# R2P_Sonar_module.net
KiCad netlist of a schematic drawn in EAGLE
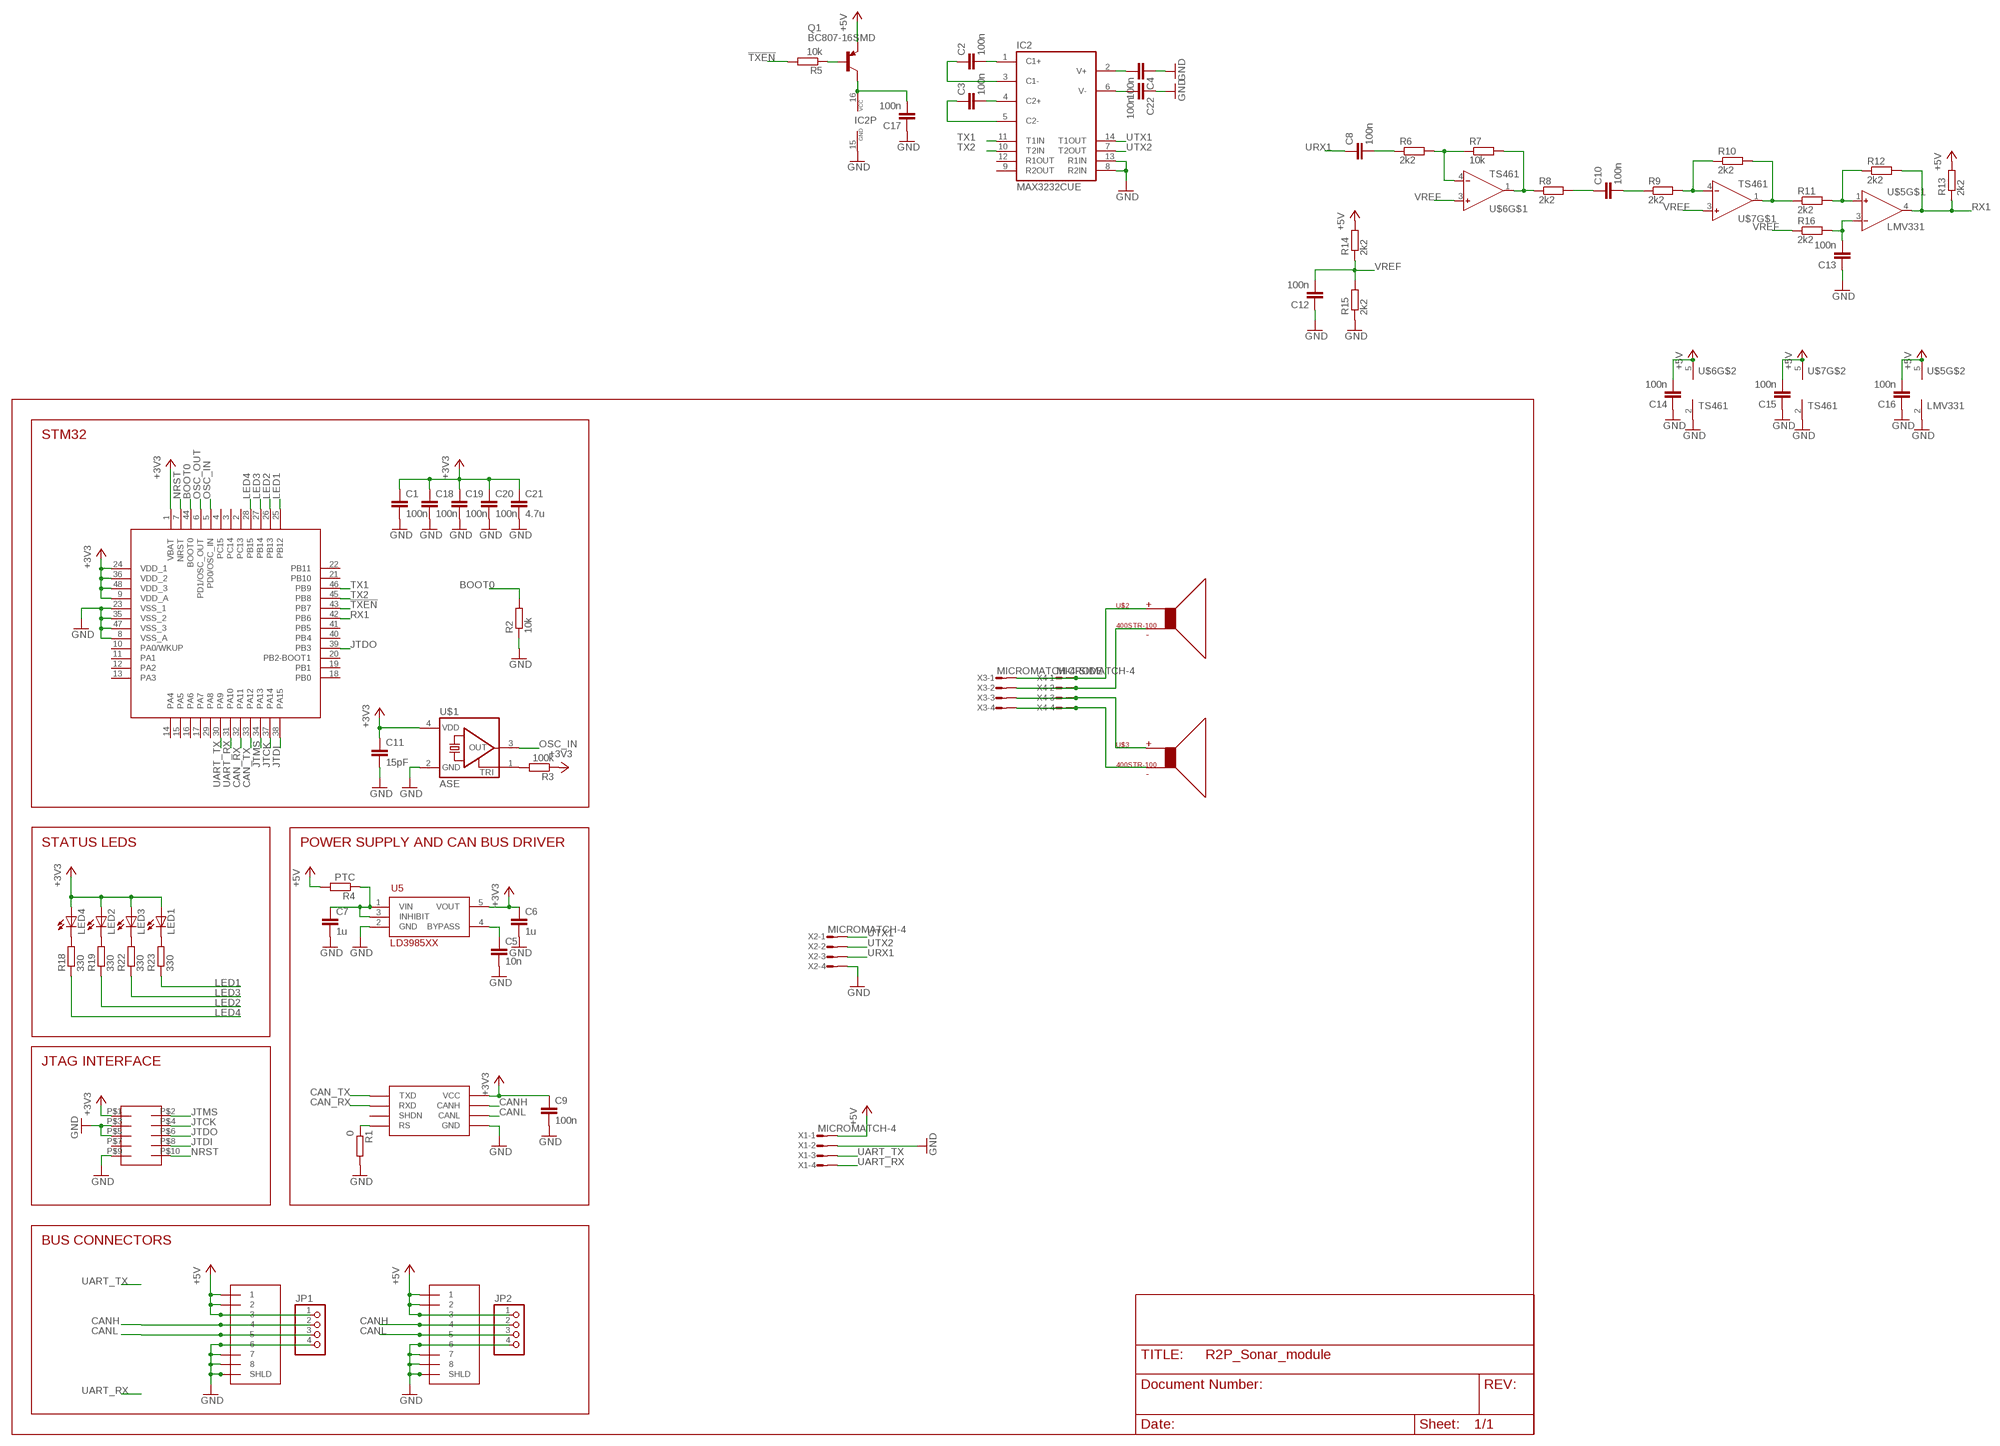
[diagram p0: schematic, sheet 1]

(export (version "E")
  (design (tool "Eeschema 10.0.6"))
  (components
    (comp (ref "1")
      (value "RJ45-43860")
      (footprint "eagle-import:0438600010")
      (libsource (lib "eagle-import") (part "RJ45-43860"))
    )
    (comp (ref "2")
      (value "RJ45-43860")
      (footprint "eagle-import:0438600010")
      (libsource (lib "eagle-import") (part "RJ45-43860"))
    )
    (comp (ref "C1")
      (value "100n")
      (footprint "eagle-import:C0603")
      (libsource (lib "eagle-import") (part "C-EUC0603"))
    )
    (comp (ref "C2")
      (value "100n")
      (footprint "eagle-import:C0603")
      (libsource (lib "eagle-import") (part "C-EUC0603"))
    )
    (comp (ref "C3")
      (value "100n")
      (footprint "eagle-import:C0603")
      (libsource (lib "eagle-import") (part "C-EUC0603"))
    )
    (comp (ref "C4")
      (value "100n")
      (footprint "eagle-import:C0603")
      (libsource (lib "eagle-import") (part "C-EUC0603"))
    )
    (comp (ref "C5")
      (value "10n")
      (footprint "eagle-import:C0603")
      (libsource (lib "eagle-import") (part "C-EUC0603"))
    )
    (comp (ref "C6")
      (value "1u")
      (footprint "eagle-import:C0603")
      (libsource (lib "eagle-import") (part "C-EUC0603"))
    )
    (comp (ref "C7")
      (value "1u")
      (footprint "eagle-import:C0603")
      (libsource (lib "eagle-import") (part "C-EUC0603"))
    )
    (comp (ref "C8")
      (value "100n")
      (footprint "eagle-import:C0603")
      (libsource (lib "eagle-import") (part "C-EUC0603"))
    )
    (comp (ref "C9")
      (value "100n")
      (footprint "eagle-import:C0603")
      (libsource (lib "eagle-import") (part "C-EUC0603"))
    )
    (comp (ref "C10")
      (value "100n")
      (footprint "eagle-import:C0603")
      (libsource (lib "eagle-import") (part "C-EUC0603"))
    )
    (comp (ref "C11")
      (value "15pF")
      (footprint "eagle-import:C0603")
      (libsource (lib "eagle-import") (part "C-EUC0603"))
    )
    (comp (ref "C12")
      (value "100n")
      (footprint "eagle-import:C0603")
      (libsource (lib "eagle-import") (part "C-EUC0603"))
    )
    (comp (ref "C13")
      (value "100n")
      (footprint "eagle-import:C0603")
      (libsource (lib "eagle-import") (part "C-EUC0603"))
    )
    (comp (ref "C14")
      (value "100n")
      (footprint "eagle-import:C0603")
      (libsource (lib "eagle-import") (part "C-EUC0603"))
    )
    (comp (ref "C15")
      (value "100n")
      (footprint "eagle-import:C0603")
      (libsource (lib "eagle-import") (part "C-EUC0603"))
    )
    (comp (ref "C16")
      (value "100n")
      (footprint "eagle-import:C0603")
      (libsource (lib "eagle-import") (part "C-EUC0603"))
    )
    (comp (ref "C17")
      (value "100n")
      (footprint "eagle-import:C0603")
      (libsource (lib "eagle-import") (part "C-EUC0603"))
    )
    (comp (ref "C18")
      (value "100n")
      (footprint "eagle-import:C0603")
      (libsource (lib "eagle-import") (part "C-EUC0603"))
    )
    (comp (ref "C19")
      (value "100n")
      (footprint "eagle-import:C0603")
      (libsource (lib "eagle-import") (part "C-EUC0603"))
    )
    (comp (ref "C20")
      (value "100n")
      (footprint "eagle-import:C0603")
      (libsource (lib "eagle-import") (part "C-EUC0603"))
    )
    (comp (ref "C21")
      (value "4.7u")
      (footprint "eagle-import:C0805")
      (libsource (lib "eagle-import") (part "C-EUC0805"))
    )
    (comp (ref "C22")
      (value "100n")
      (footprint "eagle-import:C0603")
      (libsource (lib "eagle-import") (part "C-EUC0603"))
    )
    (comp (ref "IC2")
      (value "MAX3232CUE")
      (footprint "eagle-import:TSSOP16")
      (fields (field (name "MF") "MAXIM") (field (name "MPN") "MAX3232CUE+"))
      (libsource (lib "eagle-import") (part "MAX3232UEC"))
    )
    (comp (ref "JP1")
      (value "PINHD-1X4")
      (footprint "eagle-import:1X04")
      (libsource (lib "eagle-import") (part "PINHD-1X4"))
    )
    (comp (ref "JP2")
      (value "PINHD-1X4")
      (footprint "eagle-import:1X04")
      (libsource (lib "eagle-import") (part "PINHD-1X4"))
    )
    (comp (ref "LED1")
      (value "LEDCHIPLED_0805")
      (footprint "eagle-import:CHIPLED_0805")
      (libsource (lib "eagle-import") (part "LEDCHIPLED_0805"))
    )
    (comp (ref "LED2")
      (value "LEDCHIPLED_0805")
      (footprint "eagle-import:CHIPLED_0805")
      (libsource (lib "eagle-import") (part "LEDCHIPLED_0805"))
    )
    (comp (ref "LED3")
      (value "LEDCHIPLED_0805")
      (footprint "eagle-import:CHIPLED_0805")
      (libsource (lib "eagle-import") (part "LEDCHIPLED_0805"))
    )
    (comp (ref "LED4")
      (value "LEDCHIPLED_0805")
      (footprint "eagle-import:CHIPLED_0805")
      (libsource (lib "eagle-import") (part "LEDCHIPLED_0805"))
    )
    (comp (ref "Q1")
      (value "BC807-16SMD")
      (footprint "eagle-import:SOT23-BEC")
      (libsource (lib "eagle-import") (part "BC807SMD-16"))
    )
    (comp (ref "R1")
      (value "0")
      (footprint "eagle-import:R0603")
      (libsource (lib "eagle-import") (part "R-EU_R0603"))
    )
    (comp (ref "R2")
      (value "10k")
      (footprint "eagle-import:R0603")
      (libsource (lib "eagle-import") (part "R-EU_R0603"))
    )
    (comp (ref "R3")
      (value "100k")
      (footprint "eagle-import:R0603")
      (libsource (lib "eagle-import") (part "R-EU_R0603"))
    )
    (comp (ref "R4")
      (value "PTC")
      (footprint "eagle-import:R0603")
      (libsource (lib "eagle-import") (part "R-EU_R0603"))
    )
    (comp (ref "R5")
      (value "10k")
      (footprint "eagle-import:R0603")
      (libsource (lib "eagle-import") (part "R-EU_R0603"))
    )
    (comp (ref "R6")
      (value "2k2")
      (footprint "eagle-import:R0603")
      (libsource (lib "eagle-import") (part "R-EU_R0603"))
    )
    (comp (ref "R7")
      (value "10k")
      (footprint "eagle-import:R0603")
      (libsource (lib "eagle-import") (part "R-EU_R0603"))
    )
    (comp (ref "R8")
      (value "2k2")
      (footprint "eagle-import:R0603")
      (libsource (lib "eagle-import") (part "R-EU_R0603"))
    )
    (comp (ref "R9")
      (value "2k2")
      (footprint "eagle-import:R0603")
      (libsource (lib "eagle-import") (part "R-EU_R0603"))
    )
    (comp (ref "R10")
      (value "2k2")
      (footprint "eagle-import:R0603")
      (libsource (lib "eagle-import") (part "R-EU_R0603"))
    )
    (comp (ref "R11")
      (value "2k2")
      (footprint "eagle-import:R0603")
      (libsource (lib "eagle-import") (part "R-EU_R0603"))
    )
    (comp (ref "R12")
      (value "2k2")
      (footprint "eagle-import:R0603")
      (libsource (lib "eagle-import") (part "R-EU_R0603"))
    )
    (comp (ref "R13")
      (value "2k2")
      (footprint "eagle-import:R0603")
      (libsource (lib "eagle-import") (part "R-EU_R0603"))
    )
    (comp (ref "R14")
      (value "2k2")
      (footprint "eagle-import:R0603")
      (libsource (lib "eagle-import") (part "R-EU_R0603"))
    )
    (comp (ref "R15")
      (value "2k2")
      (footprint "eagle-import:R0603")
      (libsource (lib "eagle-import") (part "R-EU_R0603"))
    )
    (comp (ref "R16")
      (value "2k2")
      (footprint "eagle-import:R0603")
      (libsource (lib "eagle-import") (part "R-EU_R0603"))
    )
    (comp (ref "R18")
      (value "330")
      (footprint "eagle-import:R0603")
      (libsource (lib "eagle-import") (part "R-EU_R0603"))
    )
    (comp (ref "R19")
      (value "330")
      (footprint "eagle-import:R0603")
      (libsource (lib "eagle-import") (part "R-EU_R0603"))
    )
    (comp (ref "R22")
      (value "330")
      (footprint "eagle-import:R0603")
      (libsource (lib "eagle-import") (part "R-EU_R0603"))
    )
    (comp (ref "R23")
      (value "330")
      (footprint "eagle-import:R0603")
      (libsource (lib "eagle-import") (part "R-EU_R0603"))
    )
    (comp (ref "SOT1")
      (value "MAX3051")
      (footprint "eagle-import:SOT23-8L")
      (libsource (lib "eagle-import") (part "MAX3051"))
    )
    (comp (ref "U$1")
      (value "ASE")
      (footprint "eagle-import:ASE")
      (libsource (lib "eagle-import") (part "ASE"))
    )
    (comp (ref "U$2")
      (value "400STR-100")
      (footprint "eagle-import:400STR100")
      (libsource (lib "eagle-import") (part "400STR-100"))
    )
    (comp (ref "U$3")
      (value "400STR-100")
      (footprint "eagle-import:400STR100")
      (libsource (lib "eagle-import") (part "400STR-100"))
    )
    (comp (ref "U$4")
      (value "FTSH-105")
      (footprint "eagle-import:FTSH-105")
      (libsource (lib "eagle-import") (part "FTSH-105"))
    )
    (comp (ref "U$5")
      (value "LMV331")
      (footprint "eagle-import:SOT23-5L")
      (libsource (lib "eagle-import") (part "LMV331"))
    )
    (comp (ref "U$6")
      (value "TS461")
      (footprint "eagle-import:SOT23-5L")
      (libsource (lib "eagle-import") (part "TS461"))
    )
    (comp (ref "U$7")
      (value "TS461")
      (footprint "eagle-import:SOT23-5L")
      (libsource (lib "eagle-import") (part "TS461"))
    )
    (comp (ref "U1")
      (value "STM32F103CX")
      (footprint "eagle-import:LQFP48")
      (libsource (lib "eagle-import") (part "STM32F103CX"))
    )
    (comp (ref "U5")
      (value "LD3985XX")
      (footprint "eagle-import:SOT23-5L")
      (libsource (lib "eagle-import") (part "LD3985XX"))
    )
    (comp (ref "X1")
      (value "MICROMATCH-4")
      (footprint "eagle-import:MICROMATCH-4")
      (libsource (lib "eagle-import") (part "tyco_MICROMATCH-4"))
    )
    (comp (ref "X2")
      (value "MICROMATCH-4")
      (footprint "eagle-import:MICROMATCH-4")
      (libsource (lib "eagle-import") (part "tyco_MICROMATCH-4"))
    )
    (comp (ref "X3")
      (value "MICROMATCH-4-SIDE")
      (footprint "eagle-import:MICROMATCH-4-SIDE")
      (libsource (lib "eagle-import") (part "MICROMATCH-4-SIDE"))
    )
    (comp (ref "X4")
      (value "MICROMATCH-4")
      (footprint "eagle-import:MICROMATCH-4")
      (libsource (lib "eagle-import") (part "tyco_MICROMATCH-4"))
    )
  )
  (nets
    (net (code "1") (name "+3V3") (class "Default")
      (node (ref "C1") (pin "1") (pinfunction "1_1") (pintype "passive"))
      (node (ref "C11") (pin "1") (pinfunction "1_1") (pintype "passive"))
      (node (ref "C18") (pin "1") (pinfunction "1_1") (pintype "passive"))
      (node (ref "C19") (pin "1") (pinfunction "1_1") (pintype "passive"))
      (node (ref "C20") (pin "1") (pinfunction "1_1") (pintype "passive"))
      (node (ref "C21") (pin "1") (pinfunction "1_1") (pintype "passive"))
      (node (ref "C6") (pin "1") (pinfunction "1_1") (pintype "passive"))
      (node (ref "C9") (pin "1") (pinfunction "1_1") (pintype "passive"))
      (node (ref "LED1") (pin "A") (pinfunction "A_A") (pintype "passive"))
      (node (ref "LED2") (pin "A") (pinfunction "A_A") (pintype "passive"))
      (node (ref "LED3") (pin "A") (pinfunction "A_A") (pintype "passive"))
      (node (ref "LED4") (pin "A") (pinfunction "A_A") (pintype "passive"))
      (node (ref "R3") (pin "1") (pinfunction "1_1") (pintype "passive"))
      (node (ref "SOT1") (pin "P$3") (pinfunction "VCC_P$3") (pintype "bidirectional"))
      (node (ref "U$1") (pin "4") (pinfunction "VDD_4") (pintype "power_in"))
      (node (ref "U$4") (pin "P$1") (pinfunction "P$1_P$1") (pintype "bidirectional"))
      (node (ref "U1") (pin "1") (pinfunction "VBAT_1") (pintype "bidirectional"))
      (node (ref "U1") (pin "24") (pinfunction "VDD_1_24") (pintype "bidirectional"))
      (node (ref "U1") (pin "36") (pinfunction "VDD_2_36") (pintype "bidirectional"))
      (node (ref "U1") (pin "48") (pinfunction "VDD_3_48") (pintype "bidirectional"))
      (node (ref "U1") (pin "9") (pinfunction "VDD_A_9") (pintype "bidirectional"))
      (node (ref "U5") (pin "5") (pinfunction "VOUT_5") (pintype "bidirectional"))
    )
    (net (code "2") (name "+5V") (class "Default")
      (node (ref "1") (pin "P$1") (pinfunction "1_P$1") (pintype "bidirectional"))
      (node (ref "1") (pin "P$2") (pinfunction "2_P$2") (pintype "bidirectional"))
      (node (ref "1") (pin "P$3") (pinfunction "3_P$3") (pintype "bidirectional"))
      (node (ref "2") (pin "P$1") (pinfunction "1_P$1") (pintype "bidirectional"))
      (node (ref "2") (pin "P$2") (pinfunction "2_P$2") (pintype "bidirectional"))
      (node (ref "2") (pin "P$3") (pinfunction "3_P$3") (pintype "bidirectional"))
      (node (ref "C14") (pin "2") (pinfunction "2_2") (pintype "passive"))
      (node (ref "C15") (pin "2") (pinfunction "2_2") (pintype "passive"))
      (node (ref "C16") (pin "2") (pinfunction "2_2") (pintype "passive"))
      (node (ref "JP1") (pin "1") (pinfunction "1_1") (pintype "passive"))
      (node (ref "JP2") (pin "1") (pinfunction "1_1") (pintype "passive"))
      (node (ref "Q1") (pin "E") (pinfunction "E_E") (pintype "passive"))
      (node (ref "R13") (pin "2") (pinfunction "2_2") (pintype "passive"))
      (node (ref "R14") (pin "2") (pinfunction "2_2") (pintype "passive"))
      (node (ref "R4") (pin "2") (pinfunction "2_2") (pintype "passive"))
      (node (ref "U$5") (pin "5") (pinfunction "V+_5") (pintype "power_in"))
      (node (ref "U$6") (pin "5") (pinfunction "V+_5") (pintype "power_in"))
      (node (ref "U$7") (pin "5") (pinfunction "V+_5") (pintype "power_in"))
      (node (ref "X1") (pin "1") (pinfunction "S_1") (pintype "passive"))
    )
    (net (code "3") (name "/BOOT0") (class "Default")
      (node (ref "R2") (pin "2") (pinfunction "2_2") (pintype "passive"))
      (node (ref "U1") (pin "44") (pinfunction "BOOT0_44") (pintype "bidirectional"))
    )
    (net (code "4") (name "/CANH") (class "Default")
      (node (ref "1") (pin "P$4") (pinfunction "4_P$4") (pintype "bidirectional"))
      (node (ref "2") (pin "P$4") (pinfunction "4_P$4") (pintype "bidirectional"))
      (node (ref "JP1") (pin "2") (pinfunction "2_2") (pintype "passive"))
      (node (ref "JP2") (pin "2") (pinfunction "2_2") (pintype "passive"))
      (node (ref "SOT1") (pin "P$7") (pinfunction "CANH_P$7") (pintype "bidirectional"))
    )
    (net (code "5") (name "/CANL") (class "Default")
      (node (ref "1") (pin "P$5") (pinfunction "5_P$5") (pintype "bidirectional"))
      (node (ref "2") (pin "P$5") (pinfunction "5_P$5") (pintype "bidirectional"))
      (node (ref "JP1") (pin "3") (pinfunction "3_3") (pintype "passive"))
      (node (ref "JP2") (pin "3") (pinfunction "3_3") (pintype "passive"))
      (node (ref "SOT1") (pin "P$6") (pinfunction "CANL_P$6") (pintype "bidirectional"))
    )
    (net (code "6") (name "/CAN_RX") (class "Default")
      (node (ref "SOT1") (pin "P$4") (pinfunction "RXD_P$4") (pintype "bidirectional"))
      (node (ref "U1") (pin "32") (pinfunction "PA11_32") (pintype "bidirectional"))
    )
    (net (code "7") (name "/CAN_TX") (class "Default")
      (node (ref "SOT1") (pin "P$1") (pinfunction "TXD_P$1") (pintype "bidirectional"))
      (node (ref "U1") (pin "33") (pinfunction "PA12_33") (pintype "bidirectional"))
    )
    (net (code "8") (name "/JTCK") (class "Default")
      (node (ref "U$4") (pin "P$4") (pinfunction "P$4_P$4") (pintype "bidirectional"))
      (node (ref "U1") (pin "37") (pinfunction "PA14_37") (pintype "bidirectional"))
    )
    (net (code "9") (name "/JTDI") (class "Default")
      (node (ref "U$4") (pin "P$8") (pinfunction "P$8_P$8") (pintype "bidirectional"))
      (node (ref "U1") (pin "38") (pinfunction "PA15_38") (pintype "bidirectional"))
    )
    (net (code "10") (name "/JTDO") (class "Default")
      (node (ref "U$4") (pin "P$6") (pinfunction "P$6_P$6") (pintype "bidirectional"))
      (node (ref "U1") (pin "39") (pinfunction "PB3_39") (pintype "bidirectional"))
    )
    (net (code "11") (name "/JTMS") (class "Default")
      (node (ref "U$4") (pin "P$2") (pinfunction "P$2_P$2") (pintype "bidirectional"))
      (node (ref "U1") (pin "34") (pinfunction "PA13_34") (pintype "bidirectional"))
    )
    (net (code "12") (name "/LED1") (class "Default")
      (node (ref "R23") (pin "1") (pinfunction "1_1") (pintype "passive"))
      (node (ref "U1") (pin "25") (pinfunction "PB12_25") (pintype "bidirectional"))
    )
    (net (code "13") (name "/LED2") (class "Default")
      (node (ref "R19") (pin "1") (pinfunction "1_1") (pintype "passive"))
      (node (ref "U1") (pin "26") (pinfunction "PB13_26") (pintype "bidirectional"))
    )
    (net (code "14") (name "/LED3") (class "Default")
      (node (ref "R22") (pin "1") (pinfunction "1_1") (pintype "passive"))
      (node (ref "U1") (pin "27") (pinfunction "PB14_27") (pintype "bidirectional"))
    )
    (net (code "15") (name "/LED4") (class "Default")
      (node (ref "R18") (pin "1") (pinfunction "1_1") (pintype "passive"))
      (node (ref "U1") (pin "28") (pinfunction "PB15_28") (pintype "bidirectional"))
    )
    (net (code "16") (name "/NRST") (class "Default")
      (node (ref "U$4") (pin "P$10") (pinfunction "P$10_P$10") (pintype "bidirectional"))
      (node (ref "U1") (pin "7") (pinfunction "NRST_7") (pintype "bidirectional"))
    )
    (net (code "17") (name "/OSC_IN") (class "Default")
      (node (ref "U$1") (pin "3") (pinfunction "OUT_3") (pintype "output"))
      (node (ref "U1") (pin "5") (pinfunction "PD0/OSC_IN_5") (pintype "bidirectional"))
    )
    (net (code "18") (name "/OSC_OUT") (class "Default")
      (node (ref "U1") (pin "6") (pinfunction "PD1/OSC_OUT_6") (pintype "bidirectional"))
    )
    (net (code "19") (name "/RX1") (class "Default")
      (node (ref "R12") (pin "2") (pinfunction "2_2") (pintype "passive"))
      (node (ref "R13") (pin "1") (pinfunction "1_1") (pintype "passive"))
      (node (ref "U$5") (pin "4") (pinfunction "OUT_4") (pintype "output"))
      (node (ref "U1") (pin "42") (pinfunction "PB6_42") (pintype "bidirectional"))
    )
    (net (code "20") (name "/TX1") (class "Default")
      (node (ref "IC2") (pin "11") (pinfunction "T1IN_11") (pintype "input"))
      (node (ref "U1") (pin "46") (pinfunction "PB9_46") (pintype "bidirectional"))
    )
    (net (code "21") (name "/TX2") (class "Default")
      (node (ref "IC2") (pin "10") (pinfunction "T2IN_10") (pintype "input"))
      (node (ref "U1") (pin "45") (pinfunction "PB8_45") (pintype "bidirectional"))
    )
    (net (code "22") (name "/UART_RX") (class "Default")
      (node (ref "U1") (pin "31") (pinfunction "PA10_31") (pintype "bidirectional"))
      (node (ref "X1") (pin "4") (pinfunction "S_4") (pintype "passive"))
    )
    (net (code "23") (name "/UART_TX") (class "Default")
      (node (ref "U1") (pin "30") (pinfunction "PA9_30") (pintype "bidirectional"))
      (node (ref "X1") (pin "3") (pinfunction "S_3") (pintype "passive"))
    )
    (net (code "24") (name "/URX1") (class "Default")
      (node (ref "C8") (pin "1") (pinfunction "1_1") (pintype "passive"))
      (node (ref "X2") (pin "3") (pinfunction "S_3") (pintype "passive"))
    )
    (net (code "25") (name "/UTX1") (class "Default")
      (node (ref "IC2") (pin "14") (pinfunction "T1OUT_14") (pintype "output"))
      (node (ref "X2") (pin "1") (pinfunction "S_1") (pintype "passive"))
    )
    (net (code "26") (name "/UTX2") (class "Default")
      (node (ref "IC2") (pin "7") (pinfunction "T2OUT_7") (pintype "output"))
      (node (ref "X2") (pin "2") (pinfunction "S_2") (pintype "passive"))
    )
    (net (code "27") (name "/VREF") (class "Default")
      (node (ref "C12") (pin "2") (pinfunction "2_2") (pintype "passive"))
      (node (ref "R14") (pin "1") (pinfunction "1_1") (pintype "passive"))
      (node (ref "R15") (pin "2") (pinfunction "2_2") (pintype "passive"))
      (node (ref "R16") (pin "1") (pinfunction "1_1") (pintype "passive"))
      (node (ref "U$6") (pin "3") (pinfunction "IN+_3") (pintype "input"))
      (node (ref "U$7") (pin "3") (pinfunction "IN+_3") (pintype "input"))
    )
    (net (code "28") (name "/~{TXEN}") (class "Default")
      (node (ref "R5") (pin "2") (pinfunction "2_2") (pintype "passive"))
      (node (ref "U1") (pin "43") (pinfunction "PB7_43") (pintype "bidirectional"))
    )
    (net (code "29") (name "GND") (class "Default")
      (node (ref "1") (pin "P$10") (pinfunction "P$1_P$10") (pintype "power_in"))
      (node (ref "1") (pin "P$6") (pinfunction "6_P$6") (pintype "bidirectional"))
      (node (ref "1") (pin "P$7") (pinfunction "7_P$7") (pintype "bidirectional"))
      (node (ref "1") (pin "P$8") (pinfunction "8_P$8") (pintype "bidirectional"))
      (node (ref "1") (pin "P$9") (pinfunction "SHLD_P$9") (pintype "power_in"))
      (node (ref "2") (pin "P$10") (pinfunction "P$1_P$10") (pintype "power_in"))
      (node (ref "2") (pin "P$6") (pinfunction "6_P$6") (pintype "bidirectional"))
      (node (ref "2") (pin "P$7") (pinfunction "7_P$7") (pintype "bidirectional"))
      (node (ref "2") (pin "P$8") (pinfunction "8_P$8") (pintype "bidirectional"))
      (node (ref "2") (pin "P$9") (pinfunction "SHLD_P$9") (pintype "power_in"))
      (node (ref "C1") (pin "2") (pinfunction "2_2") (pintype "passive"))
      (node (ref "C11") (pin "2") (pinfunction "2_2") (pintype "passive"))
      (node (ref "C12") (pin "1") (pinfunction "1_1") (pintype "passive"))
      (node (ref "C13") (pin "1") (pinfunction "1_1") (pintype "passive"))
      (node (ref "C14") (pin "1") (pinfunction "1_1") (pintype "passive"))
      (node (ref "C15") (pin "1") (pinfunction "1_1") (pintype "passive"))
      (node (ref "C16") (pin "1") (pinfunction "1_1") (pintype "passive"))
      (node (ref "C17") (pin "1") (pinfunction "1_1") (pintype "passive"))
      (node (ref "C18") (pin "2") (pinfunction "2_2") (pintype "passive"))
      (node (ref "C19") (pin "2") (pinfunction "2_2") (pintype "passive"))
      (node (ref "C20") (pin "2") (pinfunction "2_2") (pintype "passive"))
      (node (ref "C21") (pin "2") (pinfunction "2_2") (pintype "passive"))
      (node (ref "C22") (pin "1") (pinfunction "1_1") (pintype "passive"))
      (node (ref "C4") (pin "1") (pinfunction "1_1") (pintype "passive"))
      (node (ref "C5") (pin "2") (pinfunction "2_2") (pintype "passive"))
      (node (ref "C6") (pin "2") (pinfunction "2_2") (pintype "passive"))
      (node (ref "C7") (pin "2") (pinfunction "2_2") (pintype "passive"))
      (node (ref "C9") (pin "2") (pinfunction "2_2") (pintype "passive"))
      (node (ref "IC2") (pin "13") (pinfunction "R1IN_13") (pintype "input"))
      (node (ref "IC2") (pin "15") (pinfunction "GND_15") (pintype "power_in"))
      (node (ref "IC2") (pin "8") (pinfunction "R2IN_8") (pintype "input"))
      (node (ref "JP1") (pin "4") (pinfunction "4_4") (pintype "passive"))
      (node (ref "JP2") (pin "4") (pinfunction "4_4") (pintype "passive"))
      (node (ref "R1") (pin "2") (pinfunction "2_2") (pintype "passive"))
      (node (ref "R15") (pin "1") (pinfunction "1_1") (pintype "passive"))
      (node (ref "R2") (pin "1") (pinfunction "1_1") (pintype "passive"))
      (node (ref "SOT1") (pin "P$2") (pinfunction "GND_P$2") (pintype "bidirectional"))
      (node (ref "U$1") (pin "2") (pinfunction "GND_2") (pintype "power_in"))
      (node (ref "U$4") (pin "P$3") (pinfunction "P$3_P$3") (pintype "bidirectional"))
      (node (ref "U$4") (pin "P$5") (pinfunction "P$5_P$5") (pintype "bidirectional"))
      (node (ref "U$4") (pin "P$9") (pinfunction "P$9_P$9") (pintype "bidirectional"))
      (node (ref "U$5") (pin "2") (pinfunction "V-_2") (pintype "power_in"))
      (node (ref "U$6") (pin "2") (pinfunction "V-_2") (pintype "power_in"))
      (node (ref "U$7") (pin "2") (pinfunction "V-_2") (pintype "power_in"))
      (node (ref "U1") (pin "23") (pinfunction "VSS_1_23") (pintype "bidirectional"))
      (node (ref "U1") (pin "35") (pinfunction "VSS_2_35") (pintype "bidirectional"))
      (node (ref "U1") (pin "47") (pinfunction "VSS_3_47") (pintype "bidirectional"))
      (node (ref "U1") (pin "8") (pinfunction "VSS_A_8") (pintype "bidirectional"))
      (node (ref "U5") (pin "2") (pinfunction "GND_2") (pintype "bidirectional"))
      (node (ref "X1") (pin "2") (pinfunction "S_2") (pintype "passive"))
      (node (ref "X2") (pin "4") (pinfunction "S_4") (pintype "passive"))
    )
    (net (code "30") (name "Net-(C8-Pad2)") (class "Default")
      (node (ref "C8") (pin "2") (pinfunction "2_2") (pintype "passive"))
      (node (ref "R6") (pin "1") (pinfunction "1_1") (pintype "passive"))
    )
    (net (code "31") (name "Net-(C10-Pad1)") (class "Default")
      (node (ref "C10") (pin "1") (pinfunction "1_1") (pintype "passive"))
      (node (ref "R8") (pin "2") (pinfunction "2_2") (pintype "passive"))
    )
    (net (code "32") (name "Net-(C10-Pad2)") (class "Default")
      (node (ref "C10") (pin "2") (pinfunction "2_2") (pintype "passive"))
      (node (ref "R9") (pin "1") (pinfunction "1_1") (pintype "passive"))
    )
    (net (code "33") (name "Net-(IC2A-C1+)") (class "Default")
      (node (ref "C2") (pin "2") (pinfunction "2_2") (pintype "passive"))
      (node (ref "IC2") (pin "1") (pinfunction "C1+_1") (pintype "bidirectional"))
    )
    (net (code "34") (name "Net-(IC2A-C1-)") (class "Default")
      (node (ref "C2") (pin "1") (pinfunction "1_1") (pintype "passive"))
      (node (ref "IC2") (pin "3") (pinfunction "C1-_3") (pintype "bidirectional"))
    )
    (net (code "35") (name "Net-(IC2A-C2+)") (class "Default")
      (node (ref "C3") (pin "2") (pinfunction "2_2") (pintype "passive"))
      (node (ref "IC2") (pin "4") (pinfunction "C2+_4") (pintype "bidirectional"))
    )
    (net (code "36") (name "Net-(IC2A-C2-)") (class "Default")
      (node (ref "C3") (pin "1") (pinfunction "1_1") (pintype "passive"))
      (node (ref "IC2") (pin "5") (pinfunction "C2-_5") (pintype "bidirectional"))
    )
    (net (code "37") (name "Net-(IC2A-V+)") (class "Default")
      (node (ref "C4") (pin "2") (pinfunction "2_2") (pintype "passive"))
      (node (ref "IC2") (pin "2") (pinfunction "V+_2") (pintype "bidirectional"))
    )
    (net (code "38") (name "Net-(IC2A-V-)") (class "Default")
      (node (ref "C22") (pin "2") (pinfunction "2_2") (pintype "passive"))
      (node (ref "IC2") (pin "6") (pinfunction "V-_6") (pintype "bidirectional"))
    )
    (net (code "39") (name "Net-(IC2B-VCC)") (class "Default")
      (node (ref "C17") (pin "2") (pinfunction "2_2") (pintype "passive"))
      (node (ref "IC2") (pin "16") (pinfunction "VCC_16") (pintype "power_in"))
      (node (ref "Q1") (pin "C") (pinfunction "C_C") (pintype "passive"))
    )
    (net (code "40") (name "Net-(LED1-PadC)") (class "Default")
      (node (ref "LED1") (pin "C") (pinfunction "C_C") (pintype "passive"))
      (node (ref "R23") (pin "2") (pinfunction "2_2") (pintype "passive"))
    )
    (net (code "41") (name "Net-(LED2-PadC)") (class "Default")
      (node (ref "LED2") (pin "C") (pinfunction "C_C") (pintype "passive"))
      (node (ref "R19") (pin "2") (pinfunction "2_2") (pintype "passive"))
    )
    (net (code "42") (name "Net-(LED3-PadC)") (class "Default")
      (node (ref "LED3") (pin "C") (pinfunction "C_C") (pintype "passive"))
      (node (ref "R22") (pin "2") (pinfunction "2_2") (pintype "passive"))
    )
    (net (code "43") (name "Net-(LED4-PadC)") (class "Default")
      (node (ref "LED4") (pin "C") (pinfunction "C_C") (pintype "passive"))
      (node (ref "R18") (pin "2") (pinfunction "2_2") (pintype "passive"))
    )
    (net (code "44") (name "Net-(Q1-PadB)") (class "Default")
      (node (ref "Q1") (pin "B") (pinfunction "B_B") (pintype "passive"))
      (node (ref "R5") (pin "1") (pinfunction "1_1") (pintype "passive"))
    )
    (net (code "45") (name "Net-(SOT1-RS)") (class "Default")
      (node (ref "R1") (pin "1") (pinfunction "1_1") (pintype "passive"))
      (node (ref "SOT1") (pin "P$8") (pinfunction "RS_P$8") (pintype "bidirectional"))
    )
    (net (code "46") (name "Net-(U$1-TRI)") (class "Default")
      (node (ref "R3") (pin "2") (pinfunction "2_2") (pintype "passive"))
      (node (ref "U$1") (pin "1") (pinfunction "TRI_1") (pintype "input"))
    )
    (net (code "47") (name "Net-(U$5A-IN+)") (class "Default")
      (node (ref "R11") (pin "2") (pinfunction "2_2") (pintype "passive"))
      (node (ref "R12") (pin "1") (pinfunction "1_1") (pintype "passive"))
      (node (ref "U$5") (pin "1") (pinfunction "IN+_1") (pintype "input"))
    )
    (net (code "48") (name "Net-(U$5A-IN-)") (class "Default")
      (node (ref "C13") (pin "2") (pinfunction "2_2") (pintype "passive"))
      (node (ref "R16") (pin "2") (pinfunction "2_2") (pintype "passive"))
      (node (ref "U$5") (pin "3") (pinfunction "IN-_3") (pintype "input"))
    )
    (net (code "49") (name "Net-(U$6A-IN-)") (class "Default")
      (node (ref "R6") (pin "2") (pinfunction "2_2") (pintype "passive"))
      (node (ref "R7") (pin "1") (pinfunction "1_1") (pintype "passive"))
      (node (ref "U$6") (pin "4") (pinfunction "IN-_4") (pintype "input"))
    )
    (net (code "50") (name "Net-(U$6A-OUT)") (class "Default")
      (node (ref "R7") (pin "2") (pinfunction "2_2") (pintype "passive"))
      (node (ref "R8") (pin "1") (pinfunction "1_1") (pintype "passive"))
      (node (ref "U$6") (pin "1") (pinfunction "OUT_1") (pintype "output"))
    )
    (net (code "51") (name "Net-(U$7A-IN-)") (class "Default")
      (node (ref "R10") (pin "1") (pinfunction "1_1") (pintype "passive"))
      (node (ref "R9") (pin "2") (pinfunction "2_2") (pintype "passive"))
      (node (ref "U$7") (pin "4") (pinfunction "IN-_4") (pintype "input"))
    )
    (net (code "52") (name "Net-(U$7A-OUT)") (class "Default")
      (node (ref "R10") (pin "2") (pinfunction "2_2") (pintype "passive"))
      (node (ref "R11") (pin "1") (pinfunction "1_1") (pintype "passive"))
      (node (ref "U$7") (pin "1") (pinfunction "OUT_1") (pintype "output"))
    )
    (net (code "53") (name "Net-(U5-BYPASS)") (class "Default")
      (node (ref "C5") (pin "1") (pinfunction "1_1") (pintype "passive"))
      (node (ref "U5") (pin "4") (pinfunction "BYPASS_4") (pintype "bidirectional"))
    )
    (net (code "54") (name "Net-(U5-INHIBIT)") (class "Default")
      (node (ref "C7") (pin "1") (pinfunction "1_1") (pintype "passive"))
      (node (ref "R4") (pin "1") (pinfunction "1_1") (pintype "passive"))
      (node (ref "U5") (pin "1") (pinfunction "VIN_1") (pintype "bidirectional"))
      (node (ref "U5") (pin "3") (pinfunction "INHIBIT_3") (pintype "bidirectional"))
    )
    (net (code "55") (name "Net-(X3A-S)") (class "Default")
      (node (ref "U$2") (pin "P$1") (pinfunction "P$1_P$1") (pintype "bidirectional"))
      (node (ref "X3") (pin "1") (pinfunction "S_1") (pintype "passive"))
      (node (ref "X4") (pin "1") (pinfunction "S_1") (pintype "passive"))
    )
    (net (code "56") (name "Net-(X3B-S)") (class "Default")
      (node (ref "U$2") (pin "P$2") (pinfunction "P$2_P$2") (pintype "bidirectional"))
      (node (ref "X3") (pin "2") (pinfunction "S_2") (pintype "passive"))
      (node (ref "X4") (pin "2") (pinfunction "S_2") (pintype "passive"))
    )
    (net (code "57") (name "Net-(X3C-S)") (class "Default")
      (node (ref "U$3") (pin "P$1") (pinfunction "P$1_P$1") (pintype "bidirectional"))
      (node (ref "X3") (pin "3") (pinfunction "S_3") (pintype "passive"))
      (node (ref "X4") (pin "3") (pinfunction "S_3") (pintype "passive"))
    )
    (net (code "58") (name "Net-(X3D-S)") (class "Default")
      (node (ref "U$3") (pin "P$2") (pinfunction "P$2_P$2") (pintype "bidirectional"))
      (node (ref "X3") (pin "4") (pinfunction "S_4") (pintype "passive"))
      (node (ref "X4") (pin "4") (pinfunction "S_4") (pintype "passive"))
    )
    (net (code "59") (name "unconnected-(IC2A-R1OUT-Pad12)") (class "Default")
      (node (ref "IC2") (pin "12") (pinfunction "R1OUT_12") (pintype "output"))
    )
    (net (code "60") (name "unconnected-(IC2A-R2OUT-Pad9)") (class "Default")
      (node (ref "IC2") (pin "9") (pinfunction "R2OUT_9") (pintype "output"))
    )
    (net (code "61") (name "unconnected-(SOT1-SHDN-PadP$5)") (class "Default")
      (node (ref "SOT1") (pin "P$5") (pinfunction "SHDN_P$5") (pintype "bidirectional"))
    )
    (net (code "62") (name "unconnected-(U$4-PadP$7)") (class "Default")
      (node (ref "U$4") (pin "P$7") (pinfunction "P$7_P$7") (pintype "bidirectional"))
    )
    (net (code "63") (name "unconnected-(U1-PA0{slash}WKUP-Pad10)") (class "Default")
      (node (ref "U1") (pin "10") (pinfunction "PA0/WKUP_10") (pintype "bidirectional"))
    )
    (net (code "64") (name "unconnected-(U1-PA1-Pad11)") (class "Default")
      (node (ref "U1") (pin "11") (pinfunction "PA1_11") (pintype "bidirectional"))
    )
    (net (code "65") (name "unconnected-(U1-PA2-Pad12)") (class "Default")
      (node (ref "U1") (pin "12") (pinfunction "PA2_12") (pintype "bidirectional"))
    )
    (net (code "66") (name "unconnected-(U1-PA3-Pad13)") (class "Default")
      (node (ref "U1") (pin "13") (pinfunction "PA3_13") (pintype "bidirectional"))
    )
    (net (code "67") (name "unconnected-(U1-PA4-Pad14)") (class "Default")
      (node (ref "U1") (pin "14") (pinfunction "PA4_14") (pintype "bidirectional"))
    )
    (net (code "68") (name "unconnected-(U1-PA5-Pad15)") (class "Default")
      (node (ref "U1") (pin "15") (pinfunction "PA5_15") (pintype "bidirectional"))
    )
    (net (code "69") (name "unconnected-(U1-PA6-Pad16)") (class "Default")
      (node (ref "U1") (pin "16") (pinfunction "PA6_16") (pintype "bidirectional"))
    )
    (net (code "70") (name "unconnected-(U1-PA7-Pad17)") (class "Default")
      (node (ref "U1") (pin "17") (pinfunction "PA7_17") (pintype "bidirectional"))
    )
    (net (code "71") (name "unconnected-(U1-PA8-Pad29)") (class "Default")
      (node (ref "U1") (pin "29") (pinfunction "PA8_29") (pintype "bidirectional"))
    )
    (net (code "72") (name "unconnected-(U1-PB0-Pad18)") (class "Default")
      (node (ref "U1") (pin "18") (pinfunction "PB0_18") (pintype "bidirectional"))
    )
    (net (code "73") (name "unconnected-(U1-PB1-Pad19)") (class "Default")
      (node (ref "U1") (pin "19") (pinfunction "PB1_19") (pintype "bidirectional"))
    )
    (net (code "74") (name "unconnected-(U1-PB2-BOOT1-Pad20)") (class "Default")
      (node (ref "U1") (pin "20") (pinfunction "PB2-BOOT1_20") (pintype "bidirectional"))
    )
    (net (code "75") (name "unconnected-(U1-PB4-Pad40)") (class "Default")
      (node (ref "U1") (pin "40") (pinfunction "PB4_40") (pintype "bidirectional"))
    )
    (net (code "76") (name "unconnected-(U1-PB5-Pad41)") (class "Default")
      (node (ref "U1") (pin "41") (pinfunction "PB5_41") (pintype "bidirectional"))
    )
    (net (code "77") (name "unconnected-(U1-PB10-Pad21)") (class "Default")
      (node (ref "U1") (pin "21") (pinfunction "PB10_21") (pintype "bidirectional"))
    )
    (net (code "78") (name "unconnected-(U1-PB11-Pad22)") (class "Default")
      (node (ref "U1") (pin "22") (pinfunction "PB11_22") (pintype "bidirectional"))
    )
    (net (code "79") (name "unconnected-(U1-PC13-Pad2)") (class "Default")
      (node (ref "U1") (pin "2") (pinfunction "PC13_2") (pintype "bidirectional"))
    )
    (net (code "80") (name "unconnected-(U1-PC14-Pad3)") (class "Default")
      (node (ref "U1") (pin "3") (pinfunction "PC14_3") (pintype "bidirectional"))
    )
    (net (code "81") (name "unconnected-(U1-PC15-Pad4)") (class "Default")
      (node (ref "U1") (pin "4") (pinfunction "PC15_4") (pintype "bidirectional"))
    )
  )
)
